# Mainboard.net
KiCad netlist of a schematic drawn in EAGLE
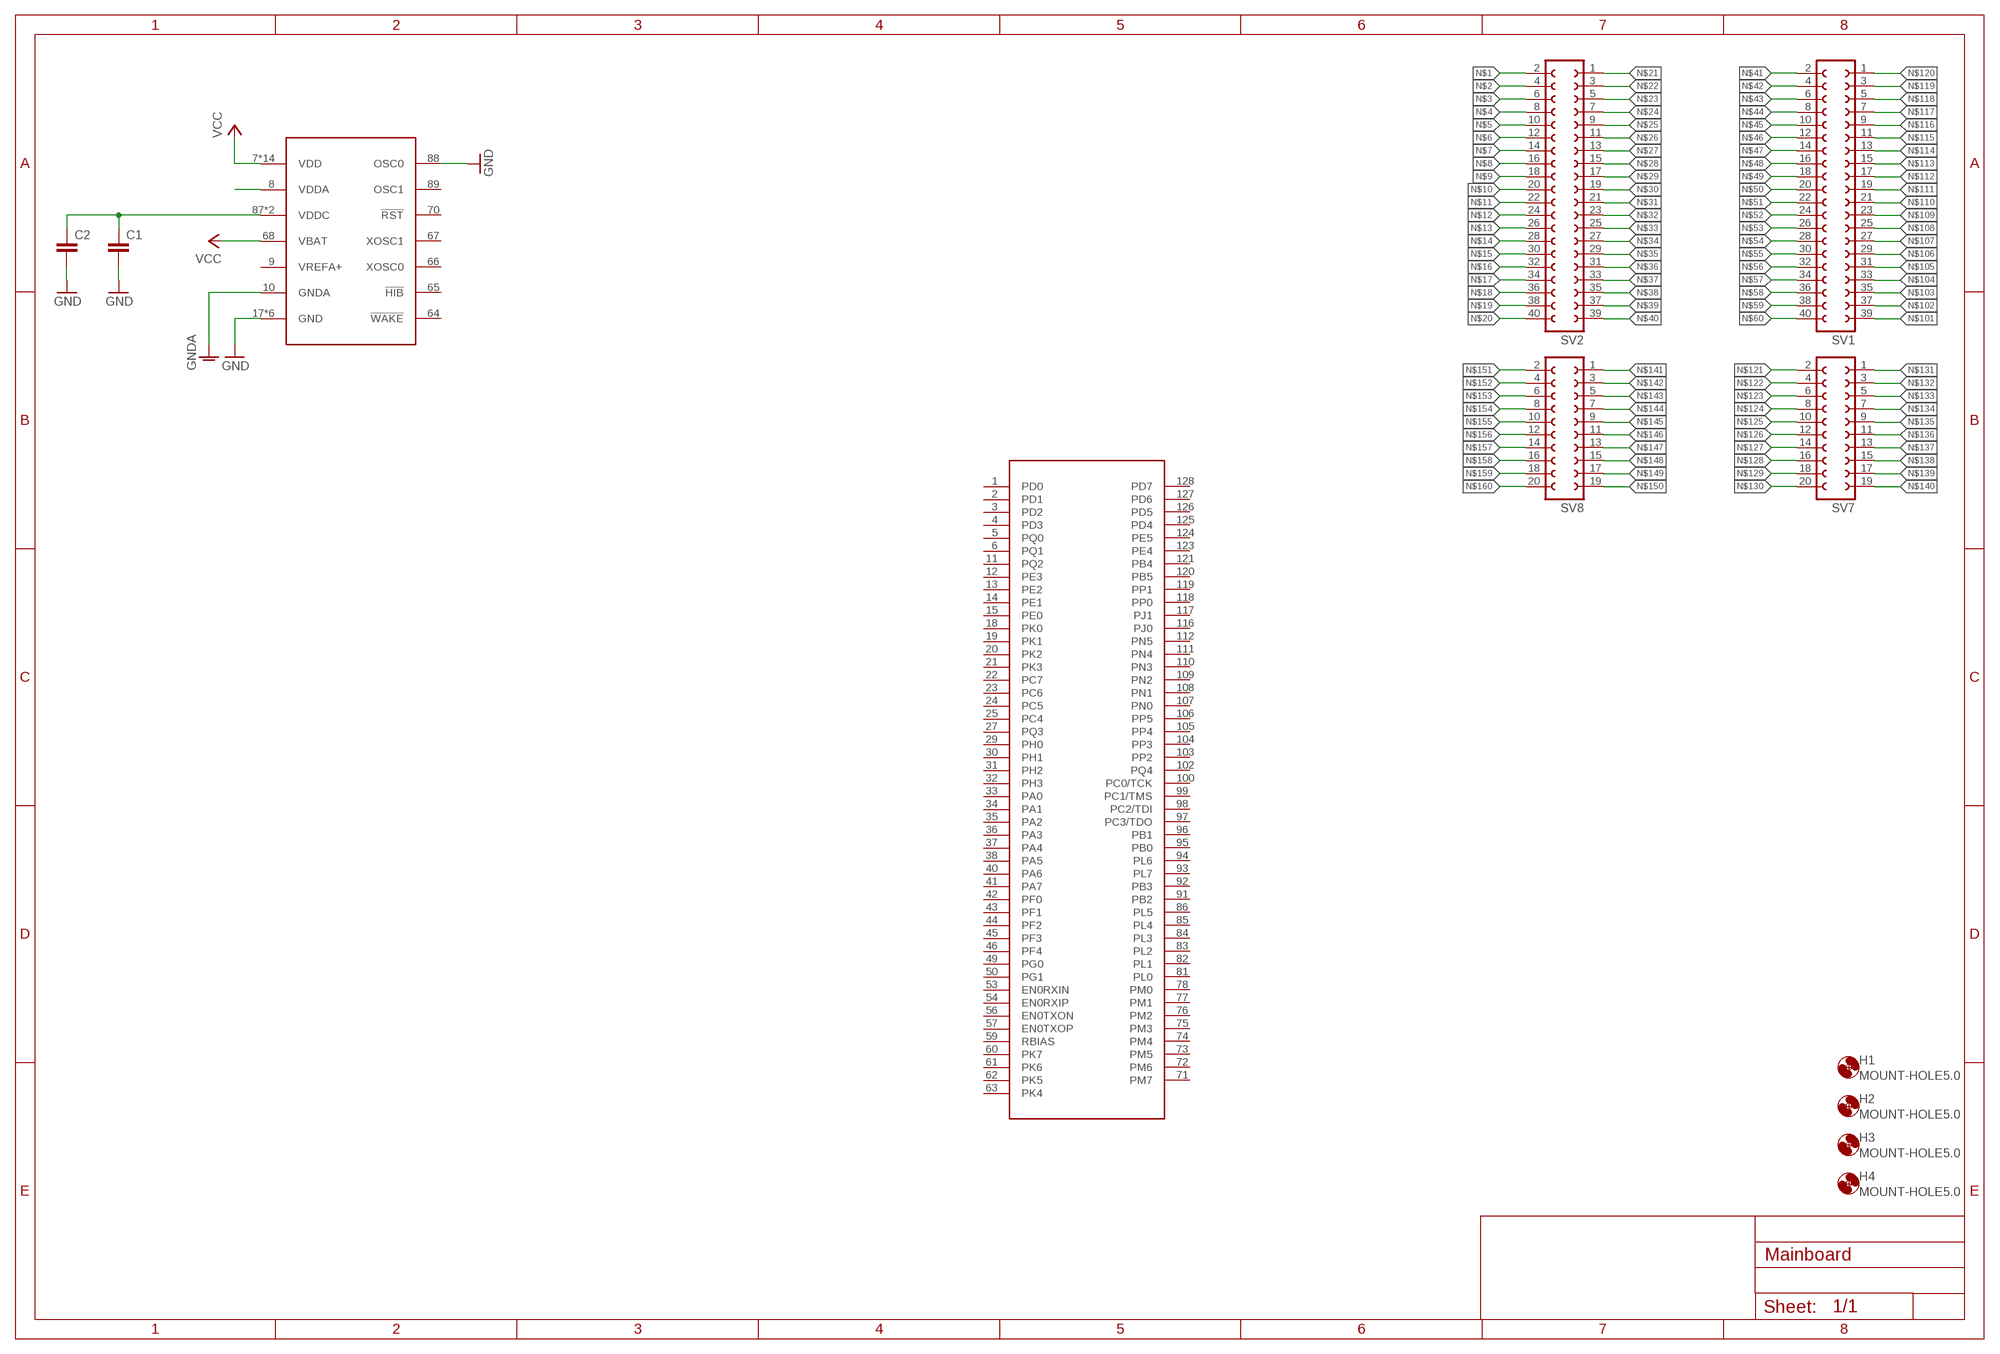
[diagram p0: schematic, sheet 1]

(export (version "E")
  (design (tool "Eeschema 10.0.6"))
  (components
    (comp (ref "C1")
      (value "C-EUC0805")
      (footprint "eagle-import:C0805")
      (libsource (lib "eagle-import") (part "C-EUC0805"))
    )
    (comp (ref "C2")
      (value "C-EUC0805")
      (footprint "eagle-import:C0805")
      (libsource (lib "eagle-import") (part "C-EUC0805"))
    )
    (comp (ref "H1")
      (value "MOUNT-HOLE5.0")
      (footprint "eagle-import:5,0")
      (libsource (lib "eagle-import") (part "MOUNT-HOLE5.0"))
    )
    (comp (ref "H2")
      (value "MOUNT-HOLE5.0")
      (footprint "eagle-import:5,0")
      (libsource (lib "eagle-import") (part "MOUNT-HOLE5.0"))
    )
    (comp (ref "H3")
      (value "MOUNT-HOLE5.0")
      (footprint "eagle-import:5,0")
      (libsource (lib "eagle-import") (part "MOUNT-HOLE5.0"))
    )
    (comp (ref "H4")
      (value "MOUNT-HOLE5.0")
      (footprint "eagle-import:5,0")
      (libsource (lib "eagle-import") (part "MOUNT-HOLE5.0"))
    )
    (comp (ref "SV1")
      (value "FE20-2")
      (footprint "eagle-import:FE20-2")
      (libsource (lib "eagle-import") (part "FE20-2"))
    )
    (comp (ref "SV2")
      (value "FE20-2")
      (footprint "eagle-import:FE20-2")
      (libsource (lib "eagle-import") (part "FE20-2"))
    )
    (comp (ref "SV7")
      (value "FE10-2")
      (footprint "eagle-import:FE10-2")
      (fields (field (name "OC_FARNELL") "unknown") (field (name "OC_NEWARK") "unknown"))
      (libsource (lib "eagle-import") (part "FE10-2"))
    )
    (comp (ref "SV8")
      (value "FE10-2")
      (footprint "eagle-import:FE10-2")
      (fields (field (name "OC_FARNELL") "unknown") (field (name "OC_NEWARK") "unknown"))
      (libsource (lib "eagle-import") (part "FE10-2"))
    )
    (comp (ref "U$1")
      (value "TM4C1294KCPDT")
      (footprint "eagle-import:TQFP128")
      (libsource (lib "eagle-import") (part "TM4C1294KCPDT"))
    )
  )
  (nets
    (net (code "1") (name "/VREFA+") (class "Default")
      (node (ref "U$1") (pin "9") (pinfunction "VREFA+_9") (pintype "power_in"))
    )
    (net (code "2") (name "GND") (class "Default")
      (node (ref "C1") (pin "2") (pinfunction "2_2") (pintype "passive"))
      (node (ref "C2") (pin "2") (pinfunction "2_2") (pintype "passive"))
      (node (ref "U$1") (pin "114") (pinfunction "GND_114") (pintype "power_in"))
      (node (ref "U$1") (pin "17") (pinfunction "GND_17") (pintype "power_in"))
      (node (ref "U$1") (pin "48") (pinfunction "GND_48") (pintype "power_in"))
      (node (ref "U$1") (pin "55") (pinfunction "GND_55") (pintype "power_in"))
      (node (ref "U$1") (pin "58") (pinfunction "GND_58") (pintype "power_in"))
      (node (ref "U$1") (pin "80") (pinfunction "GND_80") (pintype "power_in"))
      (node (ref "U$1") (pin "88") (pinfunction "OSC0_88") (pintype "bidirectional"))
    )
    (net (code "3") (name "GNDA") (class "Default")
      (node (ref "U$1") (pin "10") (pinfunction "GNDA_10") (pintype "power_in"))
    )
    (net (code "4") (name "N$1") (class "Default")
      (node (ref "SV2") (pin "2") (pinfunction "2_2") (pintype "passive"))
    )
    (net (code "5") (name "N$2") (class "Default")
      (node (ref "SV2") (pin "4") (pinfunction "4_4") (pintype "passive"))
    )
    (net (code "6") (name "N$3") (class "Default")
      (node (ref "SV2") (pin "6") (pinfunction "6_6") (pintype "passive"))
    )
    (net (code "7") (name "N$4") (class "Default")
      (node (ref "SV2") (pin "8") (pinfunction "8_8") (pintype "passive"))
    )
    (net (code "8") (name "N$5") (class "Default")
      (node (ref "SV2") (pin "10") (pinfunction "10_10") (pintype "passive"))
    )
    (net (code "9") (name "N$6") (class "Default")
      (node (ref "SV2") (pin "12") (pinfunction "12_12") (pintype "passive"))
    )
    (net (code "10") (name "N$7") (class "Default")
      (node (ref "SV2") (pin "14") (pinfunction "14_14") (pintype "passive"))
    )
    (net (code "11") (name "N$8") (class "Default")
      (node (ref "SV2") (pin "16") (pinfunction "16_16") (pintype "passive"))
    )
    (net (code "12") (name "N$9") (class "Default")
      (node (ref "SV2") (pin "18") (pinfunction "18_18") (pintype "passive"))
    )
    (net (code "13") (name "N$10") (class "Default")
      (node (ref "SV2") (pin "20") (pinfunction "20_20") (pintype "passive"))
    )
    (net (code "14") (name "N$11") (class "Default")
      (node (ref "SV2") (pin "22") (pinfunction "22_22") (pintype "passive"))
    )
    (net (code "15") (name "N$12") (class "Default")
      (node (ref "SV2") (pin "24") (pinfunction "24_24") (pintype "passive"))
    )
    (net (code "16") (name "N$13") (class "Default")
      (node (ref "SV2") (pin "26") (pinfunction "26_26") (pintype "passive"))
    )
    (net (code "17") (name "N$14") (class "Default")
      (node (ref "SV2") (pin "28") (pinfunction "28_28") (pintype "passive"))
    )
    (net (code "18") (name "N$15") (class "Default")
      (node (ref "SV2") (pin "30") (pinfunction "30_30") (pintype "passive"))
    )
    (net (code "19") (name "N$16") (class "Default")
      (node (ref "SV2") (pin "32") (pinfunction "32_32") (pintype "passive"))
    )
    (net (code "20") (name "N$17") (class "Default")
      (node (ref "SV2") (pin "34") (pinfunction "34_34") (pintype "passive"))
    )
    (net (code "21") (name "N$18") (class "Default")
      (node (ref "SV2") (pin "36") (pinfunction "36_36") (pintype "passive"))
    )
    (net (code "22") (name "N$19") (class "Default")
      (node (ref "SV2") (pin "38") (pinfunction "38_38") (pintype "passive"))
    )
    (net (code "23") (name "N$20") (class "Default")
      (node (ref "SV2") (pin "40") (pinfunction "40_40") (pintype "passive"))
    )
    (net (code "24") (name "N$21") (class "Default")
      (node (ref "SV2") (pin "1") (pinfunction "1_1") (pintype "passive"))
    )
    (net (code "25") (name "N$22") (class "Default")
      (node (ref "SV2") (pin "3") (pinfunction "3_3") (pintype "passive"))
    )
    (net (code "26") (name "N$23") (class "Default")
      (node (ref "SV2") (pin "5") (pinfunction "5_5") (pintype "passive"))
    )
    (net (code "27") (name "N$24") (class "Default")
      (node (ref "SV2") (pin "7") (pinfunction "7_7") (pintype "passive"))
    )
    (net (code "28") (name "N$25") (class "Default")
      (node (ref "SV2") (pin "9") (pinfunction "9_9") (pintype "passive"))
    )
    (net (code "29") (name "N$26") (class "Default")
      (node (ref "SV2") (pin "11") (pinfunction "11_11") (pintype "passive"))
    )
    (net (code "30") (name "N$27") (class "Default")
      (node (ref "SV2") (pin "13") (pinfunction "13_13") (pintype "passive"))
    )
    (net (code "31") (name "N$28") (class "Default")
      (node (ref "SV2") (pin "15") (pinfunction "15_15") (pintype "passive"))
    )
    (net (code "32") (name "N$29") (class "Default")
      (node (ref "SV2") (pin "17") (pinfunction "17_17") (pintype "passive"))
    )
    (net (code "33") (name "N$30") (class "Default")
      (node (ref "SV2") (pin "19") (pinfunction "19_19") (pintype "passive"))
    )
    (net (code "34") (name "N$31") (class "Default")
      (node (ref "SV2") (pin "21") (pinfunction "21_21") (pintype "passive"))
    )
    (net (code "35") (name "N$32") (class "Default")
      (node (ref "SV2") (pin "23") (pinfunction "23_23") (pintype "passive"))
    )
    (net (code "36") (name "N$33") (class "Default")
      (node (ref "SV2") (pin "25") (pinfunction "25_25") (pintype "passive"))
    )
    (net (code "37") (name "N$34") (class "Default")
      (node (ref "SV2") (pin "27") (pinfunction "27_27") (pintype "passive"))
    )
    (net (code "38") (name "N$35") (class "Default")
      (node (ref "SV2") (pin "29") (pinfunction "29_29") (pintype "passive"))
    )
    (net (code "39") (name "N$36") (class "Default")
      (node (ref "SV2") (pin "31") (pinfunction "31_31") (pintype "passive"))
    )
    (net (code "40") (name "N$37") (class "Default")
      (node (ref "SV2") (pin "33") (pinfunction "33_33") (pintype "passive"))
    )
    (net (code "41") (name "N$38") (class "Default")
      (node (ref "SV2") (pin "35") (pinfunction "35_35") (pintype "passive"))
    )
    (net (code "42") (name "N$39") (class "Default")
      (node (ref "SV2") (pin "37") (pinfunction "37_37") (pintype "passive"))
    )
    (net (code "43") (name "N$40") (class "Default")
      (node (ref "SV2") (pin "39") (pinfunction "39_39") (pintype "passive"))
    )
    (net (code "44") (name "N$41") (class "Default")
      (node (ref "SV1") (pin "2") (pinfunction "2_2") (pintype "passive"))
    )
    (net (code "45") (name "N$42") (class "Default")
      (node (ref "SV1") (pin "4") (pinfunction "4_4") (pintype "passive"))
    )
    (net (code "46") (name "N$43") (class "Default")
      (node (ref "SV1") (pin "6") (pinfunction "6_6") (pintype "passive"))
    )
    (net (code "47") (name "N$44") (class "Default")
      (node (ref "SV1") (pin "8") (pinfunction "8_8") (pintype "passive"))
    )
    (net (code "48") (name "N$45") (class "Default")
      (node (ref "SV1") (pin "10") (pinfunction "10_10") (pintype "passive"))
    )
    (net (code "49") (name "N$46") (class "Default")
      (node (ref "SV1") (pin "12") (pinfunction "12_12") (pintype "passive"))
    )
    (net (code "50") (name "N$47") (class "Default")
      (node (ref "SV1") (pin "14") (pinfunction "14_14") (pintype "passive"))
    )
    (net (code "51") (name "N$48") (class "Default")
      (node (ref "SV1") (pin "16") (pinfunction "16_16") (pintype "passive"))
    )
    (net (code "52") (name "N$49") (class "Default")
      (node (ref "SV1") (pin "18") (pinfunction "18_18") (pintype "passive"))
    )
    (net (code "53") (name "N$50") (class "Default")
      (node (ref "SV1") (pin "20") (pinfunction "20_20") (pintype "passive"))
    )
    (net (code "54") (name "N$51") (class "Default")
      (node (ref "SV1") (pin "22") (pinfunction "22_22") (pintype "passive"))
    )
    (net (code "55") (name "N$52") (class "Default")
      (node (ref "SV1") (pin "24") (pinfunction "24_24") (pintype "passive"))
    )
    (net (code "56") (name "N$53") (class "Default")
      (node (ref "SV1") (pin "26") (pinfunction "26_26") (pintype "passive"))
    )
    (net (code "57") (name "N$54") (class "Default")
      (node (ref "SV1") (pin "28") (pinfunction "28_28") (pintype "passive"))
    )
    (net (code "58") (name "N$55") (class "Default")
      (node (ref "SV1") (pin "30") (pinfunction "30_30") (pintype "passive"))
    )
    (net (code "59") (name "N$56") (class "Default")
      (node (ref "SV1") (pin "32") (pinfunction "32_32") (pintype "passive"))
    )
    (net (code "60") (name "N$57") (class "Default")
      (node (ref "SV1") (pin "34") (pinfunction "34_34") (pintype "passive"))
    )
    (net (code "61") (name "N$58") (class "Default")
      (node (ref "SV1") (pin "36") (pinfunction "36_36") (pintype "passive"))
    )
    (net (code "62") (name "N$59") (class "Default")
      (node (ref "SV1") (pin "38") (pinfunction "38_38") (pintype "passive"))
    )
    (net (code "63") (name "N$60") (class "Default")
      (node (ref "SV1") (pin "40") (pinfunction "40_40") (pintype "passive"))
    )
    (net (code "64") (name "N$101") (class "Default")
      (node (ref "SV1") (pin "39") (pinfunction "39_39") (pintype "passive"))
    )
    (net (code "65") (name "N$102") (class "Default")
      (node (ref "SV1") (pin "37") (pinfunction "37_37") (pintype "passive"))
    )
    (net (code "66") (name "N$103") (class "Default")
      (node (ref "SV1") (pin "35") (pinfunction "35_35") (pintype "passive"))
    )
    (net (code "67") (name "N$104") (class "Default")
      (node (ref "SV1") (pin "33") (pinfunction "33_33") (pintype "passive"))
    )
    (net (code "68") (name "N$105") (class "Default")
      (node (ref "SV1") (pin "31") (pinfunction "31_31") (pintype "passive"))
    )
    (net (code "69") (name "N$106") (class "Default")
      (node (ref "SV1") (pin "29") (pinfunction "29_29") (pintype "passive"))
    )
    (net (code "70") (name "N$107") (class "Default")
      (node (ref "SV1") (pin "27") (pinfunction "27_27") (pintype "passive"))
    )
    (net (code "71") (name "N$108") (class "Default")
      (node (ref "SV1") (pin "25") (pinfunction "25_25") (pintype "passive"))
    )
    (net (code "72") (name "N$109") (class "Default")
      (node (ref "SV1") (pin "23") (pinfunction "23_23") (pintype "passive"))
    )
    (net (code "73") (name "N$110") (class "Default")
      (node (ref "SV1") (pin "21") (pinfunction "21_21") (pintype "passive"))
    )
    (net (code "74") (name "N$111") (class "Default")
      (node (ref "SV1") (pin "19") (pinfunction "19_19") (pintype "passive"))
    )
    (net (code "75") (name "N$112") (class "Default")
      (node (ref "SV1") (pin "17") (pinfunction "17_17") (pintype "passive"))
    )
    (net (code "76") (name "N$113") (class "Default")
      (node (ref "SV1") (pin "15") (pinfunction "15_15") (pintype "passive"))
    )
    (net (code "77") (name "N$114") (class "Default")
      (node (ref "SV1") (pin "13") (pinfunction "13_13") (pintype "passive"))
    )
    (net (code "78") (name "N$115") (class "Default")
      (node (ref "SV1") (pin "11") (pinfunction "11_11") (pintype "passive"))
    )
    (net (code "79") (name "N$116") (class "Default")
      (node (ref "SV1") (pin "9") (pinfunction "9_9") (pintype "passive"))
    )
    (net (code "80") (name "N$117") (class "Default")
      (node (ref "SV1") (pin "7") (pinfunction "7_7") (pintype "passive"))
    )
    (net (code "81") (name "N$118") (class "Default")
      (node (ref "SV1") (pin "5") (pinfunction "5_5") (pintype "passive"))
    )
    (net (code "82") (name "N$119") (class "Default")
      (node (ref "SV1") (pin "3") (pinfunction "3_3") (pintype "passive"))
    )
    (net (code "83") (name "N$120") (class "Default")
      (node (ref "SV1") (pin "1") (pinfunction "1_1") (pintype "passive"))
    )
    (net (code "84") (name "N$121") (class "Default")
      (node (ref "SV7") (pin "2") (pinfunction "2_2") (pintype "passive"))
    )
    (net (code "85") (name "N$122") (class "Default")
      (node (ref "SV7") (pin "4") (pinfunction "4_4") (pintype "passive"))
    )
    (net (code "86") (name "N$123") (class "Default")
      (node (ref "SV7") (pin "6") (pinfunction "6_6") (pintype "passive"))
    )
    (net (code "87") (name "N$124") (class "Default")
      (node (ref "SV7") (pin "8") (pinfunction "8_8") (pintype "passive"))
    )
    (net (code "88") (name "N$125") (class "Default")
      (node (ref "SV7") (pin "10") (pinfunction "10_10") (pintype "passive"))
    )
    (net (code "89") (name "N$126") (class "Default")
      (node (ref "SV7") (pin "12") (pinfunction "12_12") (pintype "passive"))
    )
    (net (code "90") (name "N$127") (class "Default")
      (node (ref "SV7") (pin "14") (pinfunction "14_14") (pintype "passive"))
    )
    (net (code "91") (name "N$128") (class "Default")
      (node (ref "SV7") (pin "16") (pinfunction "16_16") (pintype "passive"))
    )
    (net (code "92") (name "N$129") (class "Default")
      (node (ref "SV7") (pin "18") (pinfunction "18_18") (pintype "passive"))
    )
    (net (code "93") (name "N$130") (class "Default")
      (node (ref "SV7") (pin "20") (pinfunction "20_20") (pintype "passive"))
    )
    (net (code "94") (name "N$131") (class "Default")
      (node (ref "SV7") (pin "1") (pinfunction "1_1") (pintype "passive"))
    )
    (net (code "95") (name "N$132") (class "Default")
      (node (ref "SV7") (pin "3") (pinfunction "3_3") (pintype "passive"))
    )
    (net (code "96") (name "N$133") (class "Default")
      (node (ref "SV7") (pin "5") (pinfunction "5_5") (pintype "passive"))
    )
    (net (code "97") (name "N$134") (class "Default")
      (node (ref "SV7") (pin "7") (pinfunction "7_7") (pintype "passive"))
    )
    (net (code "98") (name "N$135") (class "Default")
      (node (ref "SV7") (pin "9") (pinfunction "9_9") (pintype "passive"))
    )
    (net (code "99") (name "N$136") (class "Default")
      (node (ref "SV7") (pin "11") (pinfunction "11_11") (pintype "passive"))
    )
    (net (code "100") (name "N$137") (class "Default")
      (node (ref "SV7") (pin "13") (pinfunction "13_13") (pintype "passive"))
    )
    (net (code "101") (name "N$138") (class "Default")
      (node (ref "SV7") (pin "15") (pinfunction "15_15") (pintype "passive"))
    )
    (net (code "102") (name "N$139") (class "Default")
      (node (ref "SV7") (pin "17") (pinfunction "17_17") (pintype "passive"))
    )
    (net (code "103") (name "N$140") (class "Default")
      (node (ref "SV7") (pin "19") (pinfunction "19_19") (pintype "passive"))
    )
    (net (code "104") (name "N$141") (class "Default")
      (node (ref "SV8") (pin "1") (pinfunction "1_1") (pintype "passive"))
    )
    (net (code "105") (name "N$142") (class "Default")
      (node (ref "SV8") (pin "3") (pinfunction "3_3") (pintype "passive"))
    )
    (net (code "106") (name "N$143") (class "Default")
      (node (ref "SV8") (pin "5") (pinfunction "5_5") (pintype "passive"))
    )
    (net (code "107") (name "N$144") (class "Default")
      (node (ref "SV8") (pin "7") (pinfunction "7_7") (pintype "passive"))
    )
    (net (code "108") (name "N$145") (class "Default")
      (node (ref "SV8") (pin "9") (pinfunction "9_9") (pintype "passive"))
    )
    (net (code "109") (name "N$146") (class "Default")
      (node (ref "SV8") (pin "11") (pinfunction "11_11") (pintype "passive"))
    )
    (net (code "110") (name "N$147") (class "Default")
      (node (ref "SV8") (pin "13") (pinfunction "13_13") (pintype "passive"))
    )
    (net (code "111") (name "N$148") (class "Default")
      (node (ref "SV8") (pin "15") (pinfunction "15_15") (pintype "passive"))
    )
    (net (code "112") (name "N$149") (class "Default")
      (node (ref "SV8") (pin "17") (pinfunction "17_17") (pintype "passive"))
    )
    (net (code "113") (name "N$150") (class "Default")
      (node (ref "SV8") (pin "19") (pinfunction "19_19") (pintype "passive"))
    )
    (net (code "114") (name "N$151") (class "Default")
      (node (ref "SV8") (pin "2") (pinfunction "2_2") (pintype "passive"))
    )
    (net (code "115") (name "N$152") (class "Default")
      (node (ref "SV8") (pin "4") (pinfunction "4_4") (pintype "passive"))
    )
    (net (code "116") (name "N$153") (class "Default")
      (node (ref "SV8") (pin "6") (pinfunction "6_6") (pintype "passive"))
    )
    (net (code "117") (name "N$154") (class "Default")
      (node (ref "SV8") (pin "8") (pinfunction "8_8") (pintype "passive"))
    )
    (net (code "118") (name "N$155") (class "Default")
      (node (ref "SV8") (pin "10") (pinfunction "10_10") (pintype "passive"))
    )
    (net (code "119") (name "N$156") (class "Default")
      (node (ref "SV8") (pin "12") (pinfunction "12_12") (pintype "passive"))
    )
    (net (code "120") (name "N$157") (class "Default")
      (node (ref "SV8") (pin "14") (pinfunction "14_14") (pintype "passive"))
    )
    (net (code "121") (name "N$158") (class "Default")
      (node (ref "SV8") (pin "16") (pinfunction "16_16") (pintype "passive"))
    )
    (net (code "122") (name "N$159") (class "Default")
      (node (ref "SV8") (pin "18") (pinfunction "18_18") (pintype "passive"))
    )
    (net (code "123") (name "N$160") (class "Default")
      (node (ref "SV8") (pin "20") (pinfunction "20_20") (pintype "passive"))
    )
    (net (code "124") (name "Net-(C1-Pad1)") (class "Default")
      (node (ref "C1") (pin "1") (pinfunction "1_1") (pintype "passive"))
      (node (ref "C2") (pin "1") (pinfunction "1_1") (pintype "passive"))
      (node (ref "U$1") (pin "115") (pinfunction "VDDC_115") (pintype "power_in"))
      (node (ref "U$1") (pin "87") (pinfunction "VDDC_87") (pintype "power_in"))
    )
    (net (code "125") (name "VCC") (class "Default")
      (node (ref "U$1") (pin "101") (pinfunction "VDD_101") (pintype "power_in"))
      (node (ref "U$1") (pin "113") (pinfunction "VDD_113") (pintype "power_in"))
      (node (ref "U$1") (pin "122") (pinfunction "VDD_122") (pintype "power_in"))
      (node (ref "U$1") (pin "16") (pinfunction "VDD_16") (pintype "power_in"))
      (node (ref "U$1") (pin "26") (pinfunction "VDD_26") (pintype "power_in"))
      (node (ref "U$1") (pin "28") (pinfunction "VDD_28") (pintype "power_in"))
      (node (ref "U$1") (pin "39") (pinfunction "VDD_39") (pintype "power_in"))
      (node (ref "U$1") (pin "47") (pinfunction "VDD_47") (pintype "power_in"))
      (node (ref "U$1") (pin "51") (pinfunction "VDD_51") (pintype "power_in"))
      (node (ref "U$1") (pin "52") (pinfunction "VDD_52") (pintype "power_in"))
      (node (ref "U$1") (pin "68") (pinfunction "VBAT_68") (pintype "power_in"))
      (node (ref "U$1") (pin "69") (pinfunction "VDD_69") (pintype "power_in"))
      (node (ref "U$1") (pin "7") (pinfunction "VDD_7") (pintype "power_in"))
      (node (ref "U$1") (pin "79") (pinfunction "VDD_79") (pintype "power_in"))
      (node (ref "U$1") (pin "90") (pinfunction "VDD_90") (pintype "power_in"))
    )
    (net (code "126") (name "unconnected-(U$1A-EN0RXIN-Pad53)") (class "Default")
      (node (ref "U$1") (pin "53") (pinfunction "EN0RXIN_53") (pintype "bidirectional"))
    )
    (net (code "127") (name "unconnected-(U$1A-EN0RXIP-Pad54)") (class "Default")
      (node (ref "U$1") (pin "54") (pinfunction "EN0RXIP_54") (pintype "bidirectional"))
    )
    (net (code "128") (name "unconnected-(U$1A-EN0TXON-Pad56)") (class "Default")
      (node (ref "U$1") (pin "56") (pinfunction "EN0TXON_56") (pintype "bidirectional"))
    )
    (net (code "129") (name "unconnected-(U$1A-EN0TXOP-Pad57)") (class "Default")
      (node (ref "U$1") (pin "57") (pinfunction "EN0TXOP_57") (pintype "bidirectional"))
    )
    (net (code "130") (name "unconnected-(U$1A-PA0-Pad33)") (class "Default")
      (node (ref "U$1") (pin "33") (pinfunction "PA0_33") (pintype "bidirectional"))
    )
    (net (code "131") (name "unconnected-(U$1A-PA1-Pad34)") (class "Default")
      (node (ref "U$1") (pin "34") (pinfunction "PA1_34") (pintype "bidirectional"))
    )
    (net (code "132") (name "unconnected-(U$1A-PA2-Pad35)") (class "Default")
      (node (ref "U$1") (pin "35") (pinfunction "PA2_35") (pintype "bidirectional"))
    )
    (net (code "133") (name "unconnected-(U$1A-PA3-Pad36)") (class "Default")
      (node (ref "U$1") (pin "36") (pinfunction "PA3_36") (pintype "bidirectional"))
    )
    (net (code "134") (name "unconnected-(U$1A-PA4-Pad37)") (class "Default")
      (node (ref "U$1") (pin "37") (pinfunction "PA4_37") (pintype "bidirectional"))
    )
    (net (code "135") (name "unconnected-(U$1A-PA5-Pad38)") (class "Default")
      (node (ref "U$1") (pin "38") (pinfunction "PA5_38") (pintype "bidirectional"))
    )
    (net (code "136") (name "unconnected-(U$1A-PA6-Pad40)") (class "Default")
      (node (ref "U$1") (pin "40") (pinfunction "PA6_40") (pintype "bidirectional"))
    )
    (net (code "137") (name "unconnected-(U$1A-PA7-Pad41)") (class "Default")
      (node (ref "U$1") (pin "41") (pinfunction "PA7_41") (pintype "bidirectional"))
    )
    (net (code "138") (name "unconnected-(U$1A-PB0-Pad95)") (class "Default")
      (node (ref "U$1") (pin "95") (pinfunction "PB0_95") (pintype "bidirectional"))
    )
    (net (code "139") (name "unconnected-(U$1A-PB1-Pad96)") (class "Default")
      (node (ref "U$1") (pin "96") (pinfunction "PB1_96") (pintype "bidirectional"))
    )
    (net (code "140") (name "unconnected-(U$1A-PB2-Pad91)") (class "Default")
      (node (ref "U$1") (pin "91") (pinfunction "PB2_91") (pintype "bidirectional"))
    )
    (net (code "141") (name "unconnected-(U$1A-PB3-Pad92)") (class "Default")
      (node (ref "U$1") (pin "92") (pinfunction "PB3_92") (pintype "bidirectional"))
    )
    (net (code "142") (name "unconnected-(U$1A-PB4-Pad121)") (class "Default")
      (node (ref "U$1") (pin "121") (pinfunction "PB4_121") (pintype "bidirectional"))
    )
    (net (code "143") (name "unconnected-(U$1A-PB5-Pad120)") (class "Default")
      (node (ref "U$1") (pin "120") (pinfunction "PB5_120") (pintype "bidirectional"))
    )
    (net (code "144") (name "unconnected-(U$1A-PC0{slash}TCK-Pad100)") (class "Default")
      (node (ref "U$1") (pin "100") (pinfunction "PC0/TCK_100") (pintype "bidirectional"))
    )
    (net (code "145") (name "unconnected-(U$1A-PC1{slash}TMS-Pad99)") (class "Default")
      (node (ref "U$1") (pin "99") (pinfunction "PC1/TMS_99") (pintype "bidirectional"))
    )
    (net (code "146") (name "unconnected-(U$1A-PC2{slash}TDI-Pad98)") (class "Default")
      (node (ref "U$1") (pin "98") (pinfunction "PC2/TDI_98") (pintype "bidirectional"))
    )
    (net (code "147") (name "unconnected-(U$1A-PC3{slash}TDO-Pad97)") (class "Default")
      (node (ref "U$1") (pin "97") (pinfunction "PC3/TDO_97") (pintype "bidirectional"))
    )
    (net (code "148") (name "unconnected-(U$1A-PC4-Pad25)") (class "Default")
      (node (ref "U$1") (pin "25") (pinfunction "PC4_25") (pintype "bidirectional"))
    )
    (net (code "149") (name "unconnected-(U$1A-PC5-Pad24)") (class "Default")
      (node (ref "U$1") (pin "24") (pinfunction "PC5_24") (pintype "bidirectional"))
    )
    (net (code "150") (name "unconnected-(U$1A-PC6-Pad23)") (class "Default")
      (node (ref "U$1") (pin "23") (pinfunction "PC6_23") (pintype "bidirectional"))
    )
    (net (code "151") (name "unconnected-(U$1A-PC7-Pad22)") (class "Default")
      (node (ref "U$1") (pin "22") (pinfunction "PC7_22") (pintype "bidirectional"))
    )
    (net (code "152") (name "unconnected-(U$1A-PD0-Pad1)") (class "Default")
      (node (ref "U$1") (pin "1") (pinfunction "PD0_1") (pintype "bidirectional"))
    )
    (net (code "153") (name "unconnected-(U$1A-PD1-Pad2)") (class "Default")
      (node (ref "U$1") (pin "2") (pinfunction "PD1_2") (pintype "bidirectional"))
    )
    (net (code "154") (name "unconnected-(U$1A-PD2-Pad3)") (class "Default")
      (node (ref "U$1") (pin "3") (pinfunction "PD2_3") (pintype "bidirectional"))
    )
    (net (code "155") (name "unconnected-(U$1A-PD3-Pad4)") (class "Default")
      (node (ref "U$1") (pin "4") (pinfunction "PD3_4") (pintype "bidirectional"))
    )
    (net (code "156") (name "unconnected-(U$1A-PD4-Pad125)") (class "Default")
      (node (ref "U$1") (pin "125") (pinfunction "PD4_125") (pintype "bidirectional"))
    )
    (net (code "157") (name "unconnected-(U$1A-PD5-Pad126)") (class "Default")
      (node (ref "U$1") (pin "126") (pinfunction "PD5_126") (pintype "bidirectional"))
    )
    (net (code "158") (name "unconnected-(U$1A-PD6-Pad127)") (class "Default")
      (node (ref "U$1") (pin "127") (pinfunction "PD6_127") (pintype "bidirectional"))
    )
    (net (code "159") (name "unconnected-(U$1A-PD7-Pad128)") (class "Default")
      (node (ref "U$1") (pin "128") (pinfunction "PD7_128") (pintype "bidirectional"))
    )
    (net (code "160") (name "unconnected-(U$1A-PE0-Pad15)") (class "Default")
      (node (ref "U$1") (pin "15") (pinfunction "PE0_15") (pintype "bidirectional"))
    )
    (net (code "161") (name "unconnected-(U$1A-PE1-Pad14)") (class "Default")
      (node (ref "U$1") (pin "14") (pinfunction "PE1_14") (pintype "bidirectional"))
    )
    (net (code "162") (name "unconnected-(U$1A-PE2-Pad13)") (class "Default")
      (node (ref "U$1") (pin "13") (pinfunction "PE2_13") (pintype "bidirectional"))
    )
    (net (code "163") (name "unconnected-(U$1A-PE3-Pad12)") (class "Default")
      (node (ref "U$1") (pin "12") (pinfunction "PE3_12") (pintype "bidirectional"))
    )
    (net (code "164") (name "unconnected-(U$1A-PE4-Pad123)") (class "Default")
      (node (ref "U$1") (pin "123") (pinfunction "PE4_123") (pintype "bidirectional"))
    )
    (net (code "165") (name "unconnected-(U$1A-PE5-Pad124)") (class "Default")
      (node (ref "U$1") (pin "124") (pinfunction "PE5_124") (pintype "bidirectional"))
    )
    (net (code "166") (name "unconnected-(U$1A-PF0-Pad42)") (class "Default")
      (node (ref "U$1") (pin "42") (pinfunction "PF0_42") (pintype "bidirectional"))
    )
    (net (code "167") (name "unconnected-(U$1A-PF1-Pad43)") (class "Default")
      (node (ref "U$1") (pin "43") (pinfunction "PF1_43") (pintype "bidirectional"))
    )
    (net (code "168") (name "unconnected-(U$1A-PF2-Pad44)") (class "Default")
      (node (ref "U$1") (pin "44") (pinfunction "PF2_44") (pintype "bidirectional"))
    )
    (net (code "169") (name "unconnected-(U$1A-PF3-Pad45)") (class "Default")
      (node (ref "U$1") (pin "45") (pinfunction "PF3_45") (pintype "bidirectional"))
    )
    (net (code "170") (name "unconnected-(U$1A-PF4-Pad46)") (class "Default")
      (node (ref "U$1") (pin "46") (pinfunction "PF4_46") (pintype "bidirectional"))
    )
    (net (code "171") (name "unconnected-(U$1A-PG0-Pad49)") (class "Default")
      (node (ref "U$1") (pin "49") (pinfunction "PG0_49") (pintype "bidirectional"))
    )
    (net (code "172") (name "unconnected-(U$1A-PG1-Pad50)") (class "Default")
      (node (ref "U$1") (pin "50") (pinfunction "PG1_50") (pintype "bidirectional"))
    )
    (net (code "173") (name "unconnected-(U$1A-PH0-Pad29)") (class "Default")
      (node (ref "U$1") (pin "29") (pinfunction "PH0_29") (pintype "bidirectional"))
    )
    (net (code "174") (name "unconnected-(U$1A-PH1-Pad30)") (class "Default")
      (node (ref "U$1") (pin "30") (pinfunction "PH1_30") (pintype "bidirectional"))
    )
    (net (code "175") (name "unconnected-(U$1A-PH2-Pad31)") (class "Default")
      (node (ref "U$1") (pin "31") (pinfunction "PH2_31") (pintype "bidirectional"))
    )
    (net (code "176") (name "unconnected-(U$1A-PH3-Pad32)") (class "Default")
      (node (ref "U$1") (pin "32") (pinfunction "PH3_32") (pintype "bidirectional"))
    )
    (net (code "177") (name "unconnected-(U$1A-PJ0-Pad116)") (class "Default")
      (node (ref "U$1") (pin "116") (pinfunction "PJ0_116") (pintype "bidirectional"))
    )
    (net (code "178") (name "unconnected-(U$1A-PJ1-Pad117)") (class "Default")
      (node (ref "U$1") (pin "117") (pinfunction "PJ1_117") (pintype "bidirectional"))
    )
    (net (code "179") (name "unconnected-(U$1A-PK0-Pad18)") (class "Default")
      (node (ref "U$1") (pin "18") (pinfunction "PK0_18") (pintype "bidirectional"))
    )
    (net (code "180") (name "unconnected-(U$1A-PK1-Pad19)") (class "Default")
      (node (ref "U$1") (pin "19") (pinfunction "PK1_19") (pintype "bidirectional"))
    )
    (net (code "181") (name "unconnected-(U$1A-PK2-Pad20)") (class "Default")
      (node (ref "U$1") (pin "20") (pinfunction "PK2_20") (pintype "bidirectional"))
    )
    (net (code "182") (name "unconnected-(U$1A-PK3-Pad21)") (class "Default")
      (node (ref "U$1") (pin "21") (pinfunction "PK3_21") (pintype "bidirectional"))
    )
    (net (code "183") (name "unconnected-(U$1A-PK4-Pad63)") (class "Default")
      (node (ref "U$1") (pin "63") (pinfunction "PK4_63") (pintype "bidirectional"))
    )
    (net (code "184") (name "unconnected-(U$1A-PK5-Pad62)") (class "Default")
      (node (ref "U$1") (pin "62") (pinfunction "PK5_62") (pintype "bidirectional"))
    )
    (net (code "185") (name "unconnected-(U$1A-PK6-Pad61)") (class "Default")
      (node (ref "U$1") (pin "61") (pinfunction "PK6_61") (pintype "bidirectional"))
    )
    (net (code "186") (name "unconnected-(U$1A-PK7-Pad60)") (class "Default")
      (node (ref "U$1") (pin "60") (pinfunction "PK7_60") (pintype "bidirectional"))
    )
    (net (code "187") (name "unconnected-(U$1A-PL0-Pad81)") (class "Default")
      (node (ref "U$1") (pin "81") (pinfunction "PL0_81") (pintype "bidirectional"))
    )
    (net (code "188") (name "unconnected-(U$1A-PL1-Pad82)") (class "Default")
      (node (ref "U$1") (pin "82") (pinfunction "PL1_82") (pintype "bidirectional"))
    )
    (net (code "189") (name "unconnected-(U$1A-PL2-Pad83)") (class "Default")
      (node (ref "U$1") (pin "83") (pinfunction "PL2_83") (pintype "bidirectional"))
    )
    (net (code "190") (name "unconnected-(U$1A-PL3-Pad84)") (class "Default")
      (node (ref "U$1") (pin "84") (pinfunction "PL3_84") (pintype "bidirectional"))
    )
    (net (code "191") (name "unconnected-(U$1A-PL4-Pad85)") (class "Default")
      (node (ref "U$1") (pin "85") (pinfunction "PL4_85") (pintype "bidirectional"))
    )
    (net (code "192") (name "unconnected-(U$1A-PL5-Pad86)") (class "Default")
      (node (ref "U$1") (pin "86") (pinfunction "PL5_86") (pintype "bidirectional"))
    )
    (net (code "193") (name "unconnected-(U$1A-PL6-Pad94)") (class "Default")
      (node (ref "U$1") (pin "94") (pinfunction "PL6_94") (pintype "bidirectional"))
    )
    (net (code "194") (name "unconnected-(U$1A-PL7-Pad93)") (class "Default")
      (node (ref "U$1") (pin "93") (pinfunction "PL7_93") (pintype "bidirectional"))
    )
    (net (code "195") (name "unconnected-(U$1A-PM0-Pad78)") (class "Default")
      (node (ref "U$1") (pin "78") (pinfunction "PM0_78") (pintype "bidirectional"))
    )
    (net (code "196") (name "unconnected-(U$1A-PM1-Pad77)") (class "Default")
      (node (ref "U$1") (pin "77") (pinfunction "PM1_77") (pintype "bidirectional"))
    )
    (net (code "197") (name "unconnected-(U$1A-PM2-Pad76)") (class "Default")
      (node (ref "U$1") (pin "76") (pinfunction "PM2_76") (pintype "bidirectional"))
    )
    (net (code "198") (name "unconnected-(U$1A-PM3-Pad75)") (class "Default")
      (node (ref "U$1") (pin "75") (pinfunction "PM3_75") (pintype "bidirectional"))
    )
    (net (code "199") (name "unconnected-(U$1A-PM4-Pad74)") (class "Default")
      (node (ref "U$1") (pin "74") (pinfunction "PM4_74") (pintype "bidirectional"))
    )
    (net (code "200") (name "unconnected-(U$1A-PM5-Pad73)") (class "Default")
      (node (ref "U$1") (pin "73") (pinfunction "PM5_73") (pintype "bidirectional"))
    )
    (net (code "201") (name "unconnected-(U$1A-PM6-Pad72)") (class "Default")
      (node (ref "U$1") (pin "72") (pinfunction "PM6_72") (pintype "bidirectional"))
    )
    (net (code "202") (name "unconnected-(U$1A-PM7-Pad71)") (class "Default")
      (node (ref "U$1") (pin "71") (pinfunction "PM7_71") (pintype "bidirectional"))
    )
    (net (code "203") (name "unconnected-(U$1A-PN0-Pad107)") (class "Default")
      (node (ref "U$1") (pin "107") (pinfunction "PN0_107") (pintype "bidirectional"))
    )
    (net (code "204") (name "unconnected-(U$1A-PN1-Pad108)") (class "Default")
      (node (ref "U$1") (pin "108") (pinfunction "PN1_108") (pintype "bidirectional"))
    )
    (net (code "205") (name "unconnected-(U$1A-PN2-Pad109)") (class "Default")
      (node (ref "U$1") (pin "109") (pinfunction "PN2_109") (pintype "bidirectional"))
    )
    (net (code "206") (name "unconnected-(U$1A-PN3-Pad110)") (class "Default")
      (node (ref "U$1") (pin "110") (pinfunction "PN3_110") (pintype "bidirectional"))
    )
    (net (code "207") (name "unconnected-(U$1A-PN4-Pad111)") (class "Default")
      (node (ref "U$1") (pin "111") (pinfunction "PN4_111") (pintype "bidirectional"))
    )
    (net (code "208") (name "unconnected-(U$1A-PN5-Pad112)") (class "Default")
      (node (ref "U$1") (pin "112") (pinfunction "PN5_112") (pintype "bidirectional"))
    )
    (net (code "209") (name "unconnected-(U$1A-PP0-Pad118)") (class "Default")
      (node (ref "U$1") (pin "118") (pinfunction "PP0_118") (pintype "bidirectional"))
    )
    (net (code "210") (name "unconnected-(U$1A-PP1-Pad119)") (class "Default")
      (node (ref "U$1") (pin "119") (pinfunction "PP1_119") (pintype "bidirectional"))
    )
    (net (code "211") (name "unconnected-(U$1A-PP2-Pad103)") (class "Default")
      (node (ref "U$1") (pin "103") (pinfunction "PP2_103") (pintype "bidirectional"))
    )
    (net (code "212") (name "unconnected-(U$1A-PP3-Pad104)") (class "Default")
      (node (ref "U$1") (pin "104") (pinfunction "PP3_104") (pintype "bidirectional"))
    )
    (net (code "213") (name "unconnected-(U$1A-PP4-Pad105)") (class "Default")
      (node (ref "U$1") (pin "105") (pinfunction "PP4_105") (pintype "bidirectional"))
    )
    (net (code "214") (name "unconnected-(U$1A-PP5-Pad106)") (class "Default")
      (node (ref "U$1") (pin "106") (pinfunction "PP5_106") (pintype "bidirectional"))
    )
    (net (code "215") (name "unconnected-(U$1A-PQ0-Pad5)") (class "Default")
      (node (ref "U$1") (pin "5") (pinfunction "PQ0_5") (pintype "bidirectional"))
    )
    (net (code "216") (name "unconnected-(U$1A-PQ1-Pad6)") (class "Default")
      (node (ref "U$1") (pin "6") (pinfunction "PQ1_6") (pintype "bidirectional"))
    )
    (net (code "217") (name "unconnected-(U$1A-PQ2-Pad11)") (class "Default")
      (node (ref "U$1") (pin "11") (pinfunction "PQ2_11") (pintype "bidirectional"))
    )
    (net (code "218") (name "unconnected-(U$1A-PQ3-Pad27)") (class "Default")
      (node (ref "U$1") (pin "27") (pinfunction "PQ3_27") (pintype "bidirectional"))
    )
    (net (code "219") (name "unconnected-(U$1A-PQ4-Pad102)") (class "Default")
      (node (ref "U$1") (pin "102") (pinfunction "PQ4_102") (pintype "bidirectional"))
    )
    (net (code "220") (name "unconnected-(U$1A-RBIAS-Pad59)") (class "Default")
      (node (ref "U$1") (pin "59") (pinfunction "RBIAS_59") (pintype "bidirectional"))
    )
    (net (code "221") (name "unconnected-(U$1B-OSC1-Pad89)") (class "Default")
      (node (ref "U$1") (pin "89") (pinfunction "OSC1_89") (pintype "bidirectional"))
    )
    (net (code "222") (name "unconnected-(U$1B-VDDA-Pad8)") (class "Default")
      (node (ref "U$1") (pin "8") (pinfunction "VDDA_8") (pintype "power_in"))
    )
    (net (code "223") (name "unconnected-(U$1B-XOSC0-Pad66)") (class "Default")
      (node (ref "U$1") (pin "66") (pinfunction "XOSC0_66") (pintype "bidirectional"))
    )
    (net (code "224") (name "unconnected-(U$1B-XOSC1-Pad67)") (class "Default")
      (node (ref "U$1") (pin "67") (pinfunction "XOSC1_67") (pintype "bidirectional"))
    )
    (net (code "225") (name "unconnected-(U$1B-~{HIB}-Pad65)") (class "Default")
      (node (ref "U$1") (pin "65") (pinfunction "~{HIB}_65") (pintype "bidirectional"))
    )
    (net (code "226") (name "unconnected-(U$1B-~{RST}-Pad70)") (class "Default")
      (node (ref "U$1") (pin "70") (pinfunction "~{RST}_70") (pintype "bidirectional"))
    )
    (net (code "227") (name "unconnected-(U$1B-~{WAKE}-Pad64)") (class "Default")
      (node (ref "U$1") (pin "64") (pinfunction "~{WAKE}_64") (pintype "bidirectional"))
    )
  )
)
